# 1nuc.net
KiCad netlist of a schematic drawn in EAGLE
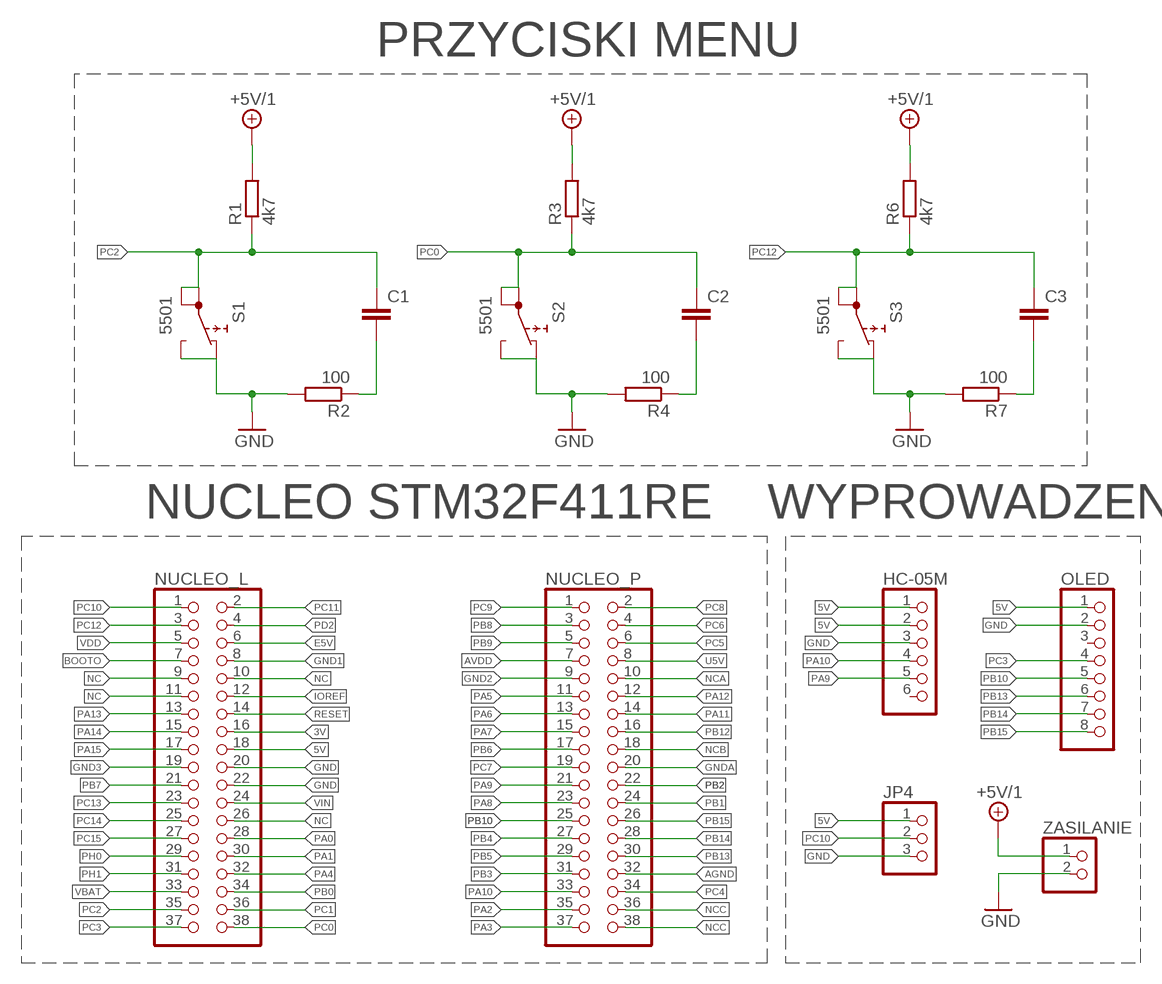
[diagram p0: schematic, sheet 1]

(export (version "E")
  (design (tool "Eeschema 10.0.6"))
  (components
    (comp (ref "C1")
      (value "C-EUC1206")
      (footprint "eagle-import:C1206")
      (libsource (lib "eagle-import") (part "C-EUC1206"))
    )
    (comp (ref "C2")
      (value "C-EUC1206")
      (footprint "eagle-import:C1206")
      (libsource (lib "eagle-import") (part "C-EUC1206"))
    )
    (comp (ref "C3")
      (value "C-EUC1206")
      (footprint "eagle-import:C1206")
      (libsource (lib "eagle-import") (part "C-EUC1206"))
    )
    (comp (ref "HC-05M")
      (value "PINHD-1X6")
      (footprint "eagle-import:1X06")
      (libsource (lib "eagle-import") (part "PINHD-1X6"))
    )
    (comp (ref "JP4")
      (value "PINHD-1X3")
      (footprint "eagle-import:1X03")
      (libsource (lib "eagle-import") (part "PINHD-1X3"))
    )
    (comp (ref "NUCLEO_L")
      (value "PINHD-2X19")
      (footprint "eagle-import:2X19")
      (libsource (lib "eagle-import") (part "PINHD-2X19"))
    )
    (comp (ref "NUCLEO_P")
      (value "PINHD-2X19")
      (footprint "eagle-import:2X19")
      (libsource (lib "eagle-import") (part "PINHD-2X19"))
    )
    (comp (ref "OLED")
      (value "PINHD-1X8")
      (footprint "eagle-import:1X08")
      (libsource (lib "eagle-import") (part "PINHD-1X8"))
    )
    (comp (ref "R1")
      (value "4k7")
      (footprint "eagle-import:R0805")
      (libsource (lib "eagle-import") (part "R-EU_R0805"))
    )
    (comp (ref "R2")
      (value "100")
      (footprint "eagle-import:R0805")
      (libsource (lib "eagle-import") (part "R-EU_R0805"))
    )
    (comp (ref "R3")
      (value "4k7")
      (footprint "eagle-import:R0805")
      (libsource (lib "eagle-import") (part "R-EU_R0805"))
    )
    (comp (ref "R4")
      (value "100")
      (footprint "eagle-import:R0805")
      (libsource (lib "eagle-import") (part "R-EU_R0805"))
    )
    (comp (ref "R6")
      (value "4k7")
      (footprint "eagle-import:R0805")
      (libsource (lib "eagle-import") (part "R-EU_R0805"))
    )
    (comp (ref "R7")
      (value "100")
      (footprint "eagle-import:R0805")
      (libsource (lib "eagle-import") (part "R-EU_R0805"))
    )
    (comp (ref "S1")
      (value "5501")
      (footprint "eagle-import:5501")
      (libsource (lib "eagle-import") (part "55?01"))
    )
    (comp (ref "S2")
      (value "5501")
      (footprint "eagle-import:5501")
      (libsource (lib "eagle-import") (part "55?01"))
    )
    (comp (ref "S3")
      (value "5501")
      (footprint "eagle-import:5501")
      (libsource (lib "eagle-import") (part "55?01"))
    )
    (comp (ref "ZASILANIE")
      (value "PINHD-1X2")
      (footprint "eagle-import:1X02")
      (libsource (lib "eagle-import") (part "PINHD-1X2"))
    )
  )
  (nets
    (net (code "1") (name "3V") (class "Default")
      (node (ref "NUCLEO_L") (pin "16") (pinfunction "16_16") (pintype "passive"))
    )
    (net (code "2") (name "5V") (class "Default")
      (node (ref "HC-05M") (pin "1") (pinfunction "1_1") (pintype "passive"))
      (node (ref "HC-05M") (pin "2") (pinfunction "2_2") (pintype "passive"))
      (node (ref "JP4") (pin "1") (pinfunction "1_1") (pintype "passive"))
      (node (ref "NUCLEO_L") (pin "18") (pinfunction "18_18") (pintype "passive"))
      (node (ref "OLED") (pin "1") (pinfunction "1_1") (pintype "passive"))
      (node (ref "R1") (pin "2") (pinfunction "2_2") (pintype "passive"))
      (node (ref "R3") (pin "2") (pinfunction "2_2") (pintype "passive"))
      (node (ref "R6") (pin "2") (pinfunction "2_2") (pintype "passive"))
      (node (ref "ZASILANIE") (pin "1") (pinfunction "1_1") (pintype "passive"))
    )
    (net (code "3") (name "AGND") (class "Default")
      (node (ref "NUCLEO_P") (pin "32") (pinfunction "32_32") (pintype "passive"))
    )
    (net (code "4") (name "AVDD") (class "Default")
      (node (ref "NUCLEO_P") (pin "7") (pinfunction "7_7") (pintype "passive"))
    )
    (net (code "5") (name "BOOTO") (class "Default")
      (node (ref "NUCLEO_L") (pin "7") (pinfunction "7_7") (pintype "passive"))
    )
    (net (code "6") (name "E5V") (class "Default")
      (node (ref "NUCLEO_L") (pin "6") (pinfunction "6_6") (pintype "passive"))
    )
    (net (code "7") (name "GND") (class "Default")
      (node (ref "HC-05M") (pin "3") (pinfunction "3_3") (pintype "passive"))
      (node (ref "JP4") (pin "3") (pinfunction "3_3") (pintype "passive"))
      (node (ref "NUCLEO_L") (pin "20") (pinfunction "20_20") (pintype "passive"))
      (node (ref "NUCLEO_L") (pin "22") (pinfunction "22_22") (pintype "passive"))
      (node (ref "OLED") (pin "2") (pinfunction "2_2") (pintype "passive"))
      (node (ref "R2") (pin "2") (pinfunction "2_2") (pintype "passive"))
      (node (ref "R4") (pin "2") (pinfunction "2_2") (pintype "passive"))
      (node (ref "R7") (pin "2") (pinfunction "2_2") (pintype "passive"))
      (node (ref "S1") (pin "NC") (pinfunction "NC_NC") (pintype "passive"))
      (node (ref "S1") (pin "NO") (pinfunction "NO_NO") (pintype "passive"))
      (node (ref "S2") (pin "NC") (pinfunction "NC_NC") (pintype "passive"))
      (node (ref "S2") (pin "NO") (pinfunction "NO_NO") (pintype "passive"))
      (node (ref "S3") (pin "NC") (pinfunction "NC_NC") (pintype "passive"))
      (node (ref "S3") (pin "NO") (pinfunction "NO_NO") (pintype "passive"))
      (node (ref "ZASILANIE") (pin "2") (pinfunction "2_2") (pintype "passive"))
    )
    (net (code "8") (name "GND1") (class "Default")
      (node (ref "NUCLEO_L") (pin "8") (pinfunction "8_8") (pintype "passive"))
    )
    (net (code "9") (name "GND2") (class "Default")
      (node (ref "NUCLEO_P") (pin "9") (pinfunction "9_9") (pintype "passive"))
    )
    (net (code "10") (name "GND3") (class "Default")
      (node (ref "NUCLEO_L") (pin "19") (pinfunction "19_19") (pintype "passive"))
    )
    (net (code "11") (name "GNDA") (class "Default")
      (node (ref "NUCLEO_P") (pin "20") (pinfunction "20_20") (pintype "passive"))
    )
    (net (code "12") (name "IOREF") (class "Default")
      (node (ref "NUCLEO_L") (pin "12") (pinfunction "12_12") (pintype "passive"))
    )
    (net (code "13") (name "NC") (class "Default")
      (node (ref "NUCLEO_L") (pin "10") (pinfunction "10_10") (pintype "passive"))
      (node (ref "NUCLEO_L") (pin "11") (pinfunction "11_11") (pintype "passive"))
      (node (ref "NUCLEO_L") (pin "26") (pinfunction "26_26") (pintype "passive"))
      (node (ref "NUCLEO_L") (pin "9") (pinfunction "9_9") (pintype "passive"))
    )
    (net (code "14") (name "NCA") (class "Default")
      (node (ref "NUCLEO_P") (pin "10") (pinfunction "10_10") (pintype "passive"))
    )
    (net (code "15") (name "NCB") (class "Default")
      (node (ref "NUCLEO_P") (pin "18") (pinfunction "18_18") (pintype "passive"))
    )
    (net (code "16") (name "NCC") (class "Default")
      (node (ref "NUCLEO_P") (pin "36") (pinfunction "36_36") (pintype "passive"))
      (node (ref "NUCLEO_P") (pin "38") (pinfunction "38_38") (pintype "passive"))
    )
    (net (code "17") (name "Net-(C1-Pad2)") (class "Default")
      (node (ref "C1") (pin "2") (pinfunction "2_2") (pintype "passive"))
      (node (ref "R2") (pin "1") (pinfunction "1_1") (pintype "passive"))
    )
    (net (code "18") (name "Net-(C2-Pad2)") (class "Default")
      (node (ref "C2") (pin "2") (pinfunction "2_2") (pintype "passive"))
      (node (ref "R4") (pin "1") (pinfunction "1_1") (pintype "passive"))
    )
    (net (code "19") (name "Net-(C3-Pad2)") (class "Default")
      (node (ref "C3") (pin "2") (pinfunction "2_2") (pintype "passive"))
      (node (ref "R7") (pin "1") (pinfunction "1_1") (pintype "passive"))
    )
    (net (code "20") (name "PA0") (class "Default")
      (node (ref "NUCLEO_L") (pin "28") (pinfunction "28_28") (pintype "passive"))
    )
    (net (code "21") (name "PA1") (class "Default")
      (node (ref "NUCLEO_L") (pin "30") (pinfunction "30_30") (pintype "passive"))
    )
    (net (code "22") (name "PA2") (class "Default")
      (node (ref "NUCLEO_P") (pin "35") (pinfunction "35_35") (pintype "passive"))
    )
    (net (code "23") (name "PA3") (class "Default")
      (node (ref "NUCLEO_P") (pin "37") (pinfunction "37_37") (pintype "passive"))
    )
    (net (code "24") (name "PA4") (class "Default")
      (node (ref "NUCLEO_L") (pin "32") (pinfunction "32_32") (pintype "passive"))
    )
    (net (code "25") (name "PA5") (class "Default")
      (node (ref "NUCLEO_P") (pin "11") (pinfunction "11_11") (pintype "passive"))
    )
    (net (code "26") (name "PA6") (class "Default")
      (node (ref "NUCLEO_P") (pin "13") (pinfunction "13_13") (pintype "passive"))
    )
    (net (code "27") (name "PA7") (class "Default")
      (node (ref "NUCLEO_P") (pin "15") (pinfunction "15_15") (pintype "passive"))
    )
    (net (code "28") (name "PA8") (class "Default")
      (node (ref "NUCLEO_P") (pin "23") (pinfunction "23_23") (pintype "passive"))
    )
    (net (code "29") (name "PA9") (class "Default")
      (node (ref "HC-05M") (pin "5") (pinfunction "5_5") (pintype "passive"))
      (node (ref "NUCLEO_P") (pin "21") (pinfunction "21_21") (pintype "passive"))
    )
    (net (code "30") (name "PA10") (class "Default")
      (node (ref "HC-05M") (pin "4") (pinfunction "4_4") (pintype "passive"))
      (node (ref "NUCLEO_P") (pin "33") (pinfunction "33_33") (pintype "passive"))
    )
    (net (code "31") (name "PA11") (class "Default")
      (node (ref "NUCLEO_P") (pin "14") (pinfunction "14_14") (pintype "passive"))
    )
    (net (code "32") (name "PA12") (class "Default")
      (node (ref "NUCLEO_P") (pin "12") (pinfunction "12_12") (pintype "passive"))
    )
    (net (code "33") (name "PA13") (class "Default")
      (node (ref "NUCLEO_L") (pin "13") (pinfunction "13_13") (pintype "passive"))
    )
    (net (code "34") (name "PA14") (class "Default")
      (node (ref "NUCLEO_L") (pin "15") (pinfunction "15_15") (pintype "passive"))
    )
    (net (code "35") (name "PA15") (class "Default")
      (node (ref "NUCLEO_L") (pin "17") (pinfunction "17_17") (pintype "passive"))
    )
    (net (code "36") (name "PB0") (class "Default")
      (node (ref "NUCLEO_L") (pin "34") (pinfunction "34_34") (pintype "passive"))
    )
    (net (code "37") (name "PB1") (class "Default")
      (node (ref "NUCLEO_P") (pin "24") (pinfunction "24_24") (pintype "passive"))
    )
    (net (code "38") (name "PB2") (class "Default")
      (node (ref "NUCLEO_P") (pin "22") (pinfunction "22_22") (pintype "passive"))
    )
    (net (code "39") (name "PB3") (class "Default")
      (node (ref "NUCLEO_P") (pin "31") (pinfunction "31_31") (pintype "passive"))
    )
    (net (code "40") (name "PB4") (class "Default")
      (node (ref "NUCLEO_P") (pin "27") (pinfunction "27_27") (pintype "passive"))
    )
    (net (code "41") (name "PB5") (class "Default")
      (node (ref "NUCLEO_P") (pin "29") (pinfunction "29_29") (pintype "passive"))
    )
    (net (code "42") (name "PB6") (class "Default")
      (node (ref "NUCLEO_P") (pin "17") (pinfunction "17_17") (pintype "passive"))
    )
    (net (code "43") (name "PB7") (class "Default")
      (node (ref "NUCLEO_L") (pin "21") (pinfunction "21_21") (pintype "passive"))
    )
    (net (code "44") (name "PB8") (class "Default")
      (node (ref "NUCLEO_P") (pin "3") (pinfunction "3_3") (pintype "passive"))
    )
    (net (code "45") (name "PB9") (class "Default")
      (node (ref "NUCLEO_P") (pin "5") (pinfunction "5_5") (pintype "passive"))
    )
    (net (code "46") (name "PB10") (class "Default")
      (node (ref "NUCLEO_P") (pin "25") (pinfunction "25_25") (pintype "passive"))
      (node (ref "OLED") (pin "5") (pinfunction "5_5") (pintype "passive"))
    )
    (net (code "47") (name "PB12") (class "Default")
      (node (ref "NUCLEO_P") (pin "16") (pinfunction "16_16") (pintype "passive"))
    )
    (net (code "48") (name "PB13") (class "Default")
      (node (ref "NUCLEO_P") (pin "30") (pinfunction "30_30") (pintype "passive"))
      (node (ref "OLED") (pin "6") (pinfunction "6_6") (pintype "passive"))
    )
    (net (code "49") (name "PB14") (class "Default")
      (node (ref "NUCLEO_P") (pin "28") (pinfunction "28_28") (pintype "passive"))
      (node (ref "OLED") (pin "7") (pinfunction "7_7") (pintype "passive"))
    )
    (net (code "50") (name "PB15") (class "Default")
      (node (ref "NUCLEO_P") (pin "26") (pinfunction "26_26") (pintype "passive"))
      (node (ref "OLED") (pin "8") (pinfunction "8_8") (pintype "passive"))
    )
    (net (code "51") (name "PC0") (class "Default")
      (node (ref "C2") (pin "1") (pinfunction "1_1") (pintype "passive"))
      (node (ref "NUCLEO_L") (pin "38") (pinfunction "38_38") (pintype "passive"))
      (node (ref "R3") (pin "1") (pinfunction "1_1") (pintype "passive"))
      (node (ref "S2") (pin "1A") (pinfunction "1A_1A") (pintype "passive"))
      (node (ref "S2") (pin "1B") (pinfunction "1B_1B") (pintype "passive"))
    )
    (net (code "52") (name "PC1") (class "Default")
      (node (ref "NUCLEO_L") (pin "36") (pinfunction "36_36") (pintype "passive"))
    )
    (net (code "53") (name "PC2") (class "Default")
      (node (ref "C1") (pin "1") (pinfunction "1_1") (pintype "passive"))
      (node (ref "NUCLEO_L") (pin "35") (pinfunction "35_35") (pintype "passive"))
      (node (ref "R1") (pin "1") (pinfunction "1_1") (pintype "passive"))
      (node (ref "S1") (pin "1A") (pinfunction "1A_1A") (pintype "passive"))
      (node (ref "S1") (pin "1B") (pinfunction "1B_1B") (pintype "passive"))
    )
    (net (code "54") (name "PC3") (class "Default")
      (node (ref "NUCLEO_L") (pin "37") (pinfunction "37_37") (pintype "passive"))
      (node (ref "OLED") (pin "4") (pinfunction "4_4") (pintype "passive"))
    )
    (net (code "55") (name "PC4") (class "Default")
      (node (ref "NUCLEO_P") (pin "34") (pinfunction "34_34") (pintype "passive"))
    )
    (net (code "56") (name "PC5") (class "Default")
      (node (ref "NUCLEO_P") (pin "6") (pinfunction "6_6") (pintype "passive"))
    )
    (net (code "57") (name "PC6") (class "Default")
      (node (ref "NUCLEO_P") (pin "4") (pinfunction "4_4") (pintype "passive"))
    )
    (net (code "58") (name "PC7") (class "Default")
      (node (ref "NUCLEO_P") (pin "19") (pinfunction "19_19") (pintype "passive"))
    )
    (net (code "59") (name "PC8") (class "Default")
      (node (ref "NUCLEO_P") (pin "2") (pinfunction "2_2") (pintype "passive"))
    )
    (net (code "60") (name "PC9") (class "Default")
      (node (ref "NUCLEO_P") (pin "1") (pinfunction "1_1") (pintype "passive"))
    )
    (net (code "61") (name "PC10") (class "Default")
      (node (ref "JP4") (pin "2") (pinfunction "2_2") (pintype "passive"))
      (node (ref "NUCLEO_L") (pin "1") (pinfunction "1_1") (pintype "passive"))
    )
    (net (code "62") (name "PC11") (class "Default")
      (node (ref "NUCLEO_L") (pin "2") (pinfunction "2_2") (pintype "passive"))
    )
    (net (code "63") (name "PC12") (class "Default")
      (node (ref "C3") (pin "1") (pinfunction "1_1") (pintype "passive"))
      (node (ref "NUCLEO_L") (pin "3") (pinfunction "3_3") (pintype "passive"))
      (node (ref "R6") (pin "1") (pinfunction "1_1") (pintype "passive"))
      (node (ref "S3") (pin "1A") (pinfunction "1A_1A") (pintype "passive"))
      (node (ref "S3") (pin "1B") (pinfunction "1B_1B") (pintype "passive"))
    )
    (net (code "64") (name "PC13") (class "Default")
      (node (ref "NUCLEO_L") (pin "23") (pinfunction "23_23") (pintype "passive"))
    )
    (net (code "65") (name "PC14") (class "Default")
      (node (ref "NUCLEO_L") (pin "25") (pinfunction "25_25") (pintype "passive"))
    )
    (net (code "66") (name "PC15") (class "Default")
      (node (ref "NUCLEO_L") (pin "27") (pinfunction "27_27") (pintype "passive"))
    )
    (net (code "67") (name "PD2") (class "Default")
      (node (ref "NUCLEO_L") (pin "4") (pinfunction "4_4") (pintype "passive"))
    )
    (net (code "68") (name "PH0") (class "Default")
      (node (ref "NUCLEO_L") (pin "29") (pinfunction "29_29") (pintype "passive"))
    )
    (net (code "69") (name "PH1") (class "Default")
      (node (ref "NUCLEO_L") (pin "31") (pinfunction "31_31") (pintype "passive"))
    )
    (net (code "70") (name "RESET") (class "Default")
      (node (ref "NUCLEO_L") (pin "14") (pinfunction "14_14") (pintype "passive"))
    )
    (net (code "71") (name "U5V") (class "Default")
      (node (ref "NUCLEO_P") (pin "8") (pinfunction "8_8") (pintype "passive"))
    )
    (net (code "72") (name "VBAT") (class "Default")
      (node (ref "NUCLEO_L") (pin "33") (pinfunction "33_33") (pintype "passive"))
    )
    (net (code "73") (name "VDD") (class "Default")
      (node (ref "NUCLEO_L") (pin "5") (pinfunction "5_5") (pintype "passive"))
    )
    (net (code "74") (name "VIN") (class "Default")
      (node (ref "NUCLEO_L") (pin "24") (pinfunction "24_24") (pintype "passive"))
    )
    (net (code "75") (name "unconnected-(HC-05M-Pad6)") (class "Default")
      (node (ref "HC-05M") (pin "6") (pinfunction "6_6") (pintype "passive"))
    )
    (net (code "76") (name "unconnected-(OLED-Pad3)") (class "Default")
      (node (ref "OLED") (pin "3") (pinfunction "3_3") (pintype "passive"))
    )
  )
)
